# EDA.net
KiCad netlist of a schematic drawn in EasyEDA
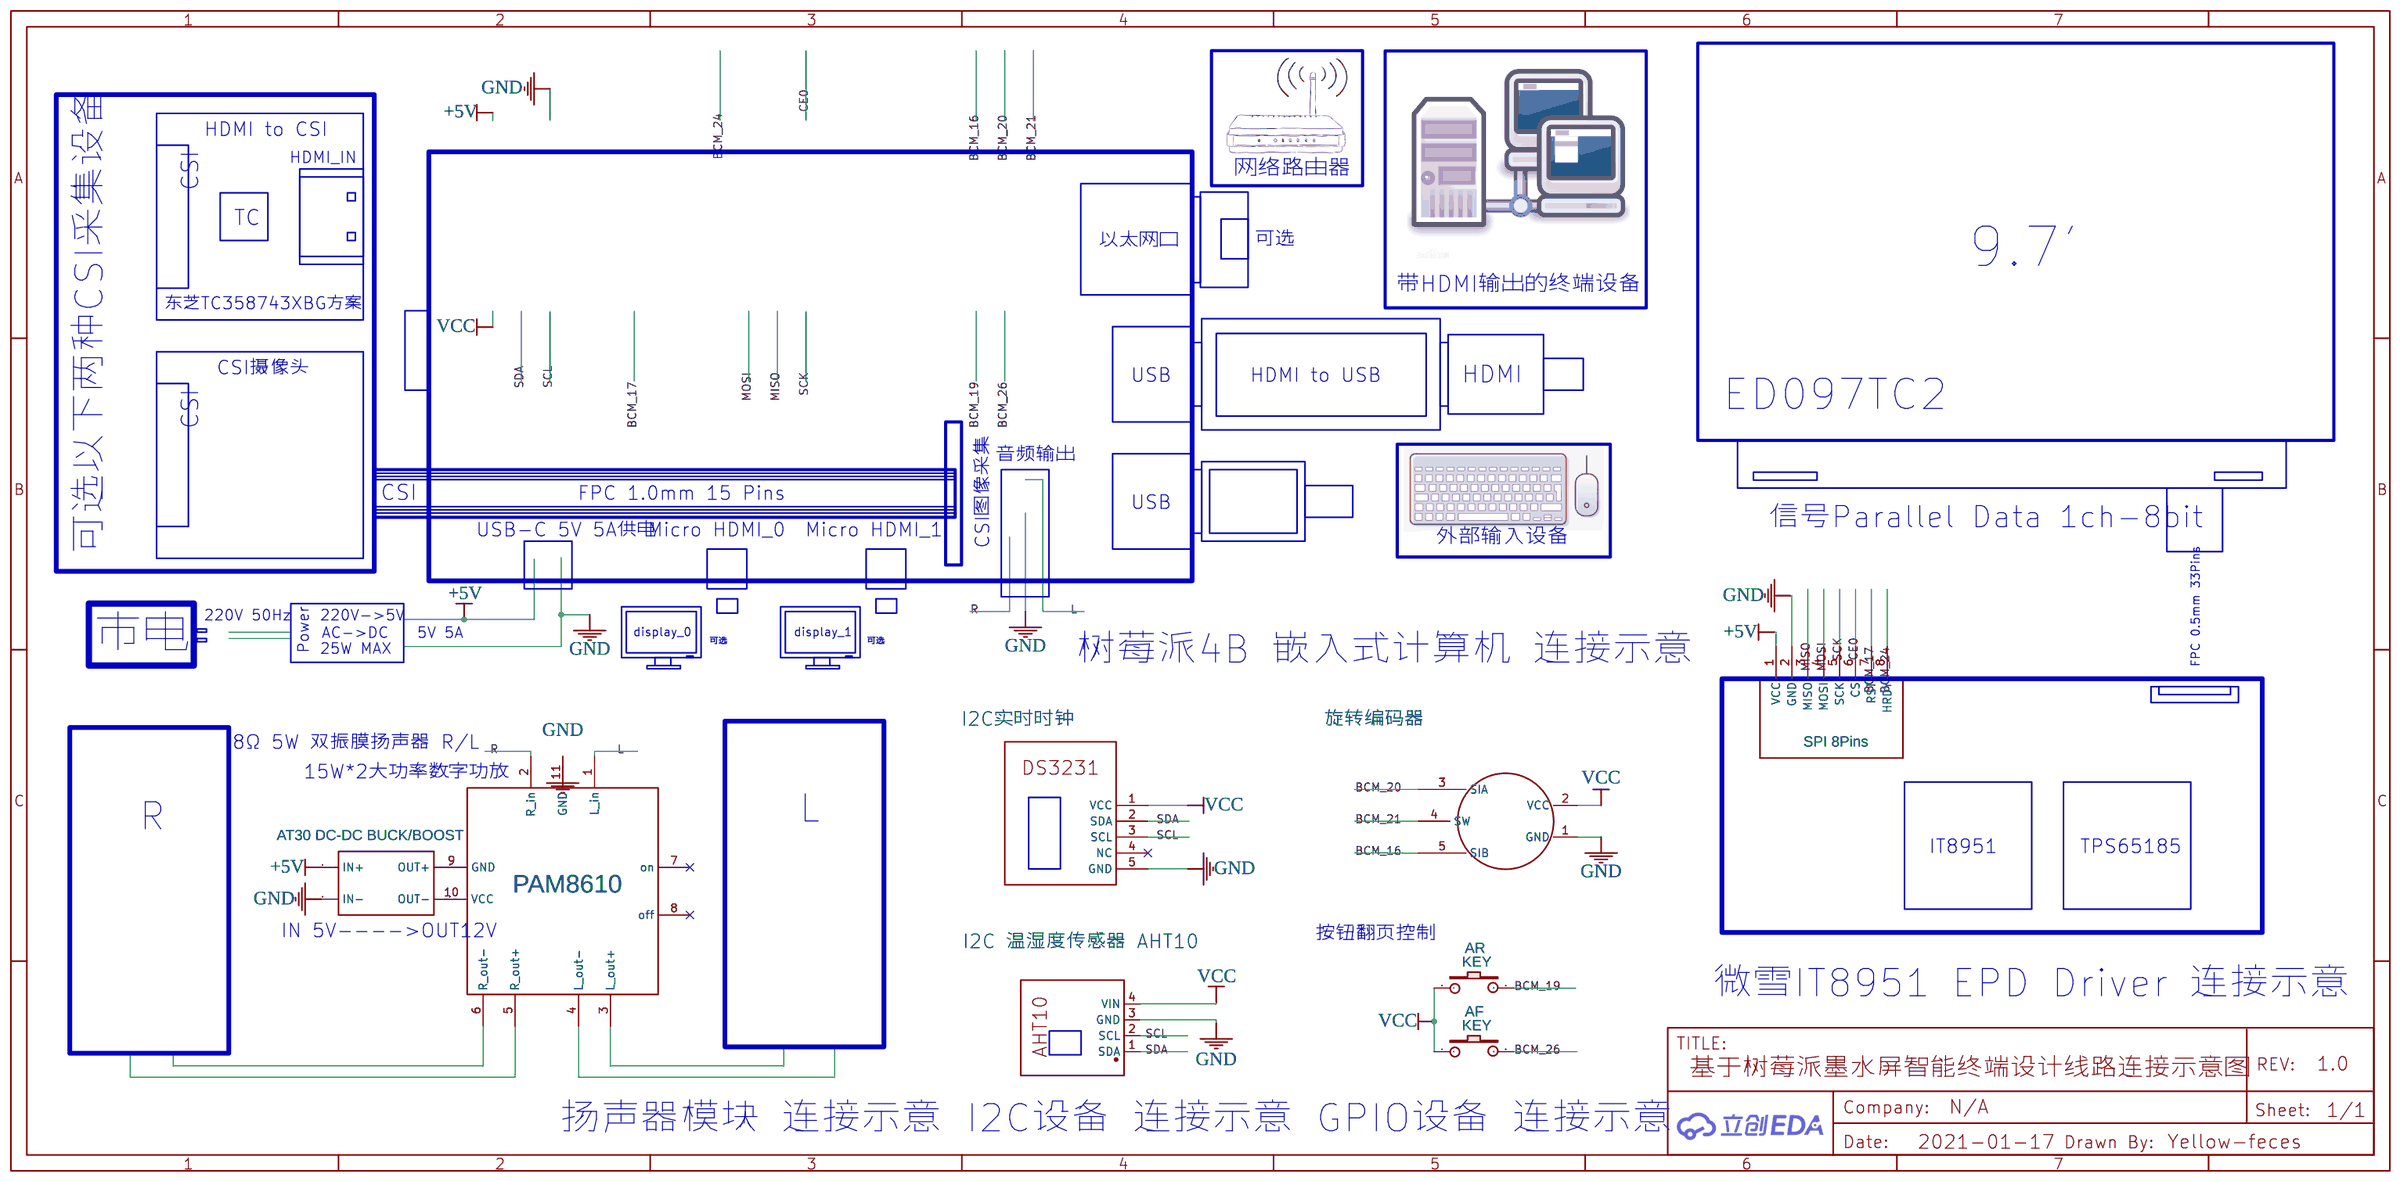
[diagram p0: schematic sheet]

(export (version "E")
  (design (tool "Eeschema 10.0.6"))
  (components
    (comp (ref "AF") (value "KEY") (libsource (lib "") (part "KEY")))
    (comp (ref "AR") (value "KEY") (libsource (lib "") (part "KEY_1")))
    (comp (ref "J1") (value "SPI 8Pins") (libsource (lib "") (part "8pin SPI 1.77")))
    (comp (ref "SW1") (value "旋转编码器") (libsource (lib "") (part "旋转编码器")))
    (comp (ref "U2")
      (value "PAM8610")
      (fields (field (name "BOM_Manufacturer Part") "New SchematicLib"))
      (libsource (lib "") (part "PAM8610_Module"))
    )
    (comp (ref "U3")
      (value "AT30 DC-DC BUCK/BOOST")
      (fields (field (name "BOM_Supplier Part") "undefined"))
      (libsource (lib "") (part "AT30"))
    )
    (comp (ref "U4")
      (value "I2C实时时钟")
      (fields (field (name "BOM_Manufacturer Part") "DS3231"))
      (libsource (lib "") (part "DS3231"))
    )
    (comp (ref "U5") (value "I2C 温湿度传感器 AHT10") (libsource (lib "") (part "AHT10")))
  )
  (nets
    (net (code "1") (name "+5V") (class "Default")
      (node (ref "J1") (pin "1") (pinfunction "VCC_1") (pintype "unspecified"))
    )
    (net (code "2") (name "/BCM_16") (class "Default")
      (node (ref "SW1") (pin "5") (pinfunction "SIB_5") (pintype "unspecified"))
    )
    (net (code "3") (name "/BCM_17") (class "Default")
      (node (ref "J1") (pin "7") (pinfunction "RST_7") (pintype "unspecified"))
    )
    (net (code "4") (name "/BCM_19") (class "Default")
      (node (ref "AR") (pin "2") (pinfunction "2_2") (pintype "unspecified"))
    )
    (net (code "5") (name "/BCM_20") (class "Default")
      (node (ref "SW1") (pin "3") (pinfunction "SIA_3") (pintype "unspecified"))
    )
    (net (code "6") (name "/BCM_21") (class "Default")
      (node (ref "SW1") (pin "4") (pinfunction "SW_4") (pintype "unspecified"))
    )
    (net (code "7") (name "/BCM_24") (class "Default")
      (node (ref "J1") (pin "8") (pinfunction "HRDY_8") (pintype "unspecified"))
    )
    (net (code "8") (name "/BCM_26") (class "Default")
      (node (ref "AF") (pin "2") (pinfunction "2_2") (pintype "unspecified"))
    )
    (net (code "9") (name "/CE0") (class "Default")
      (node (ref "J1") (pin "6") (pinfunction "CS_6") (pintype "unspecified"))
    )
    (net (code "10") (name "/L") (class "Default")
      (node (ref "U2") (pin "1") (pinfunction "L_in_1") (pintype "unspecified"))
    )
    (net (code "11") (name "/MISO") (class "Default")
      (node (ref "J1") (pin "3") (pinfunction "MISO_3") (pintype "unspecified"))
    )
    (net (code "12") (name "/MOSI") (class "Default")
      (node (ref "J1") (pin "4") (pinfunction "MOSI_4") (pintype "unspecified"))
    )
    (net (code "13") (name "/R") (class "Default")
      (node (ref "U2") (pin "2") (pinfunction "R_in_2") (pintype "unspecified"))
    )
    (net (code "14") (name "/SCK") (class "Default")
      (node (ref "J1") (pin "5") (pinfunction "SCK_5") (pintype "unspecified"))
    )
    (net (code "15") (name "/SCL") (class "Default")
      (node (ref "U4") (pin "3") (pinfunction "SCL_3") (pintype "unspecified"))
      (node (ref "U5") (pin "2") (pinfunction "SCL_2") (pintype "unspecified"))
    )
    (net (code "16") (name "/SDA") (class "Default")
      (node (ref "U4") (pin "2") (pinfunction "SDA_2") (pintype "unspecified"))
      (node (ref "U5") (pin "1") (pinfunction "SDA_1") (pintype "unspecified"))
    )
    (net (code "17") (name "GND") (class "Default")
      (node (ref "J1") (pin "2") (pinfunction "GND_2") (pintype "unspecified"))
      (node (ref "SW1") (pin "1") (pinfunction "GND_1") (pintype "unspecified"))
      (node (ref "U4") (pin "5") (pinfunction "GND_5") (pintype "unspecified"))
      (node (ref "U5") (pin "3") (pinfunction "GND_3") (pintype "unspecified"))
    )
    (net (code "18") (name "VCC") (class "Default")
      (node (ref "AF") (pin "1") (pinfunction "1_1") (pintype "unspecified"))
      (node (ref "AR") (pin "1") (pinfunction "1_1") (pintype "unspecified"))
      (node (ref "SW1") (pin "2") (pinfunction "VCC_2") (pintype "unspecified"))
      (node (ref "U4") (pin "1") (pinfunction "VCC_1") (pintype "unspecified"))
      (node (ref "U5") (pin "4") (pinfunction "VIN_4") (pintype "unspecified"))
    )
    (net (code "19") (name "unconnected-(U2-GND-Pad9)") (class "Default")
      (node (ref "U2") (pin "9") (pinfunction "GND_9") (pintype "unspecified"))
    )
    (net (code "20") (name "unconnected-(U2-GND-Pad11)") (class "Default")
      (node (ref "U2") (pin "11") (pinfunction "GND_11") (pintype "unspecified"))
    )
    (net (code "21") (name "unconnected-(U2-L_out+-Pad3)") (class "Default")
      (node (ref "U2") (pin "3") (pinfunction "L_out+_3") (pintype "unspecified"))
    )
    (net (code "22") (name "unconnected-(U2-L_out--Pad4)") (class "Default")
      (node (ref "U2") (pin "4") (pinfunction "L_out-_4") (pintype "unspecified"))
    )
    (net (code "23") (name "unconnected-(U2-R_out+-Pad5)") (class "Default")
      (node (ref "U2") (pin "5") (pinfunction "R_out+_5") (pintype "unspecified"))
    )
    (net (code "24") (name "unconnected-(U2-R_out--Pad6)") (class "Default")
      (node (ref "U2") (pin "6") (pinfunction "R_out-_6") (pintype "unspecified"))
    )
    (net (code "25") (name "unconnected-(U2-VCC-Pad10)") (class "Default")
      (node (ref "U2") (pin "10") (pinfunction "VCC_10") (pintype "unspecified"))
    )
    (net (code "26") (name "unconnected-(U2-off-Pad8)") (class "Default")
      (node (ref "U2") (pin "8") (pinfunction "off_8") (pintype "unspecified+no_connect"))
    )
    (net (code "27") (name "unconnected-(U2-on-Pad7)") (class "Default")
      (node (ref "U2") (pin "7") (pinfunction "on_7") (pintype "unspecified+no_connect"))
    )
    (net (code "28") (name "unconnected-(U3-IN+-Pad1)") (class "Default")
      (node (ref "U3") (pin "1") (pinfunction "IN+_1") (pintype "unspecified"))
    )
    (net (code "29") (name "unconnected-(U3-IN--Pad2)") (class "Default")
      (node (ref "U3") (pin "2") (pinfunction "IN-_2") (pintype "unspecified"))
    )
    (net (code "30") (name "unconnected-(U3-OUT+-Pad4)") (class "Default")
      (node (ref "U3") (pin "4") (pinfunction "OUT+_4") (pintype "unspecified"))
    )
    (net (code "31") (name "unconnected-(U3-OUT--Pad3)") (class "Default")
      (node (ref "U3") (pin "3") (pinfunction "OUT-_3") (pintype "unspecified"))
    )
    (net (code "32") (name "unconnected-(U4-NC-Pad4)") (class "Default")
      (node (ref "U4") (pin "4") (pinfunction "NC_4") (pintype "unspecified+no_connect"))
    )
  )
)
